# Main.net
KiCad netlist of a schematic drawn in Altium Designer
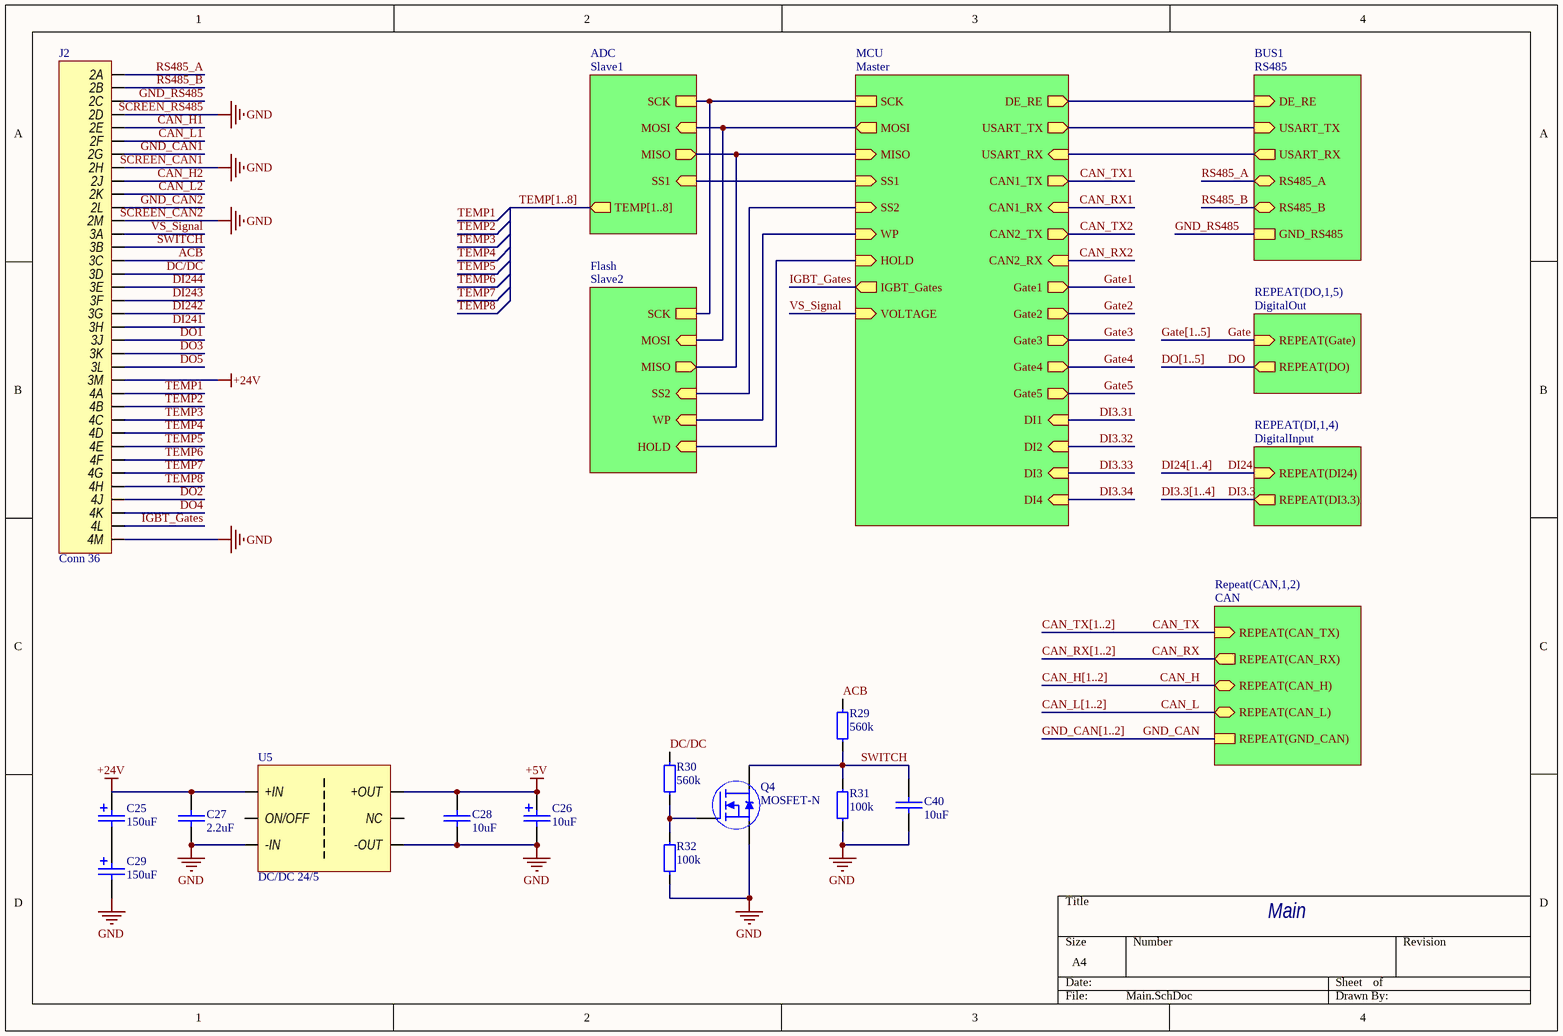
[diagram p0: Main.SchDoc]

(export (version "E")
  (design (tool "Eeschema 10.0.6"))
  (components
    (comp (ref "C25")
      (value "150uF")
      (footprint "TANTAL_D_CASE")
      (description "TECAP, 150uF, 16V, case D, 10%")
      (fields (field (name "PART NUMBER") "293D157X9010D2TE3") (field (name "MANUFACTURER") "Vishay"))
      (libsource (lib "БУНЭ") (part "Cap Tantal 150uF (SMDD)"))
    )
    (comp (ref "C26")
      (value "10uF")
      (footprint "TANTAL_C_CASE")
      (description "TECAP, 10uF, 35V, case C, 10%")
      (fields (field (name "PART NUMBER") "TECAP10/35VC10") (field (name "MANUFACTURER") "China"))
      (libsource (lib "БУНЭ") (part "Cap Tantal 10uF (SMDC)"))
    )
    (comp (ref "C27")
      (value "2.2uF")
      (footprint "0603 Capicator")
      (description "2.2uF X5R 50V 10% 0603")
      (fields
        (field (name "MANUFACTURER") "Murata Manufacturing")
        (field (name "PART NUMBER") "GRM188R61H225KE11D")
      )
      (libsource (lib "БУНЭ") (part "Cap 2.2uF (0603)"))
    )
    (comp (ref "C28")
      (value "10uF")
      (footprint "0603 Capicator")
      (description "10uF X5R 25V 20% 0603")
      (fields
        (field (name "MANUFACTURER") "Murata Manufacturing")
        (field (name "PART NUMBER") "GRM188R61E106M")
      )
      (libsource (lib "БУНЭ") (part "Cap 10uF (0603)"))
    )
    (comp (ref "C29")
      (value "150uF")
      (footprint "TANTAL_D_CASE")
      (description "TECAP, 150uF, 16V, case D, 10%")
      (fields (field (name "PART NUMBER") "293D157X9010D2TE3") (field (name "MANUFACTURER") "Vishay"))
      (libsource (lib "БУНЭ") (part "Cap Tantal 150uF (SMDD)"))
    )
    (comp (ref "C40")
      (value "10uF")
      (footprint "0603 Capicator")
      (description "10uF X5R 25V 20% 0603")
      (fields
        (field (name "MANUFACTURER") "Murata Manufacturing")
        (field (name "PART NUMBER") "GRM188R61E106M")
      )
      (libsource (lib "БУНЭ") (part "Cap 10uF (0603)"))
    )
    (comp (ref "J2")
      (value "Conn 36")
      (footprint "Molex_477320361")
      (description "Molec 36 pin PCB Header 477320361")
      (fields (field (name "MANUFACTURER") "Molex") (field (name "PART NUMBER") "477320361"))
      (libsource (lib "БУНЭ") (part "Conn 36 (Molex)"))
    )
    (comp (ref "Q4")
      (value "MOSFET-N")
      (footprint "SOT-23")
      (description "VDS 30V,  VGS Max ± 20V, RDS 27-40mΩ,")
      (fields
        (field (name "PART NUMBER") "IRLML0030TRPBF")
        (field (name "MANUFACTURER") "Infineon Technologies")
      )
      (libsource (lib "БУНЭ") (part "MOSFET-N [IRLML]"))
    )
    (comp (ref "R29")
      (value "560k")
      (footprint "0603 Resistor")
      (description "0.1W 0603 560k, 1%")
      (fields (field (name "PART NUMBER") "RC0603FR-07560KL") (field (name "MANUFACTURER") "Taiwan"))
      (libsource (lib "БУНЭ") (part "Res 560k (0603)"))
    )
    (comp (ref "R30")
      (value "560k")
      (footprint "0603 Resistor")
      (description "0.1W 0603 560k, 1%")
      (fields (field (name "PART NUMBER") "RC0603FR-07560KL") (field (name "MANUFACTURER") "Taiwan"))
      (libsource (lib "БУНЭ") (part "Res 560k (0603)"))
    )
    (comp (ref "R31")
      (value "100k")
      (footprint "0603 Resistor")
      (description "0.1W 0603 100k, 1%")
      (fields (field (name "PART NUMBER") "RC0603FR-07100KL") (field (name "MANUFACTURER") "Taiwan"))
      (libsource (lib "БУНЭ") (part "Res 100k (0603)"))
    )
    (comp (ref "R32")
      (value "100k")
      (footprint "0603 Resistor")
      (description "0.1W 0603 100k, 1%")
      (fields (field (name "PART NUMBER") "RC0603FR-07100KL") (field (name "MANUFACTURER") "Taiwan"))
      (libsource (lib "БУНЭ") (part "Res 100k (0603)"))
    )
    (comp (ref "U5")
      (value "DC/DC 24/5")
      (footprint "VDRI10(6)")
      (description "DC/DC converter 24/5 10W")
      (fields (field (name "MANUFACTURER") "Voltbricks") (field (name "PART NUMBER") "VDRI10B05"))
      (libsource (lib "БУНЭ") (part "VDRI10B05"))
    )
  )
  (nets
    (net (code "1") (name "+5V") (class "Default")
      (node (ref "C26") (pin "2") (pinfunction "2_2") (pintype "passive"))
      (node (ref "C28") (pin "2") (pinfunction "2_2") (pintype "passive"))
      (node (ref "U5") (pin "9") (pinfunction "+OUT_9") (pintype "passive"))
    )
    (net (code "2") (name "+24V") (class "Default")
      (node (ref "C25") (pin "2") (pinfunction "2_2") (pintype "passive"))
      (node (ref "C27") (pin "2") (pinfunction "2_2") (pintype "passive"))
      (node (ref "J2") (pin "3M") (pinfunction "3M_3M") (pintype "passive"))
      (node (ref "U5") (pin "16") (pinfunction "+IN_16") (pintype "passive"))
    )
    (net (code "3") (name "/ACB") (class "Default")
      (node (ref "J2") (pin "3C") (pinfunction "3C_3C") (pintype "passive"))
      (node (ref "R29") (pin "2") (pinfunction "2_2") (pintype "passive"))
    )
    (net (code "5") (name "/CAN_H1") (class "Default")
      (node (ref "J2") (pin "2E") (pinfunction "2E_2E") (pintype "passive"))
    )
    (net (code "6") (name "/CAN_H2") (class "Default")
      (node (ref "J2") (pin "2J") (pinfunction "2J_2J") (pintype "passive"))
    )
    (net (code "9") (name "/CAN_L1") (class "Default")
      (node (ref "J2") (pin "2F") (pinfunction "2F_2F") (pintype "passive"))
    )
    (net (code "10") (name "/CAN_L2") (class "Default")
      (node (ref "J2") (pin "2K") (pinfunction "2K_2K") (pintype "passive"))
    )
    (net (code "20") (name "/DC{slash}DC") (class "Default")
      (node (ref "J2") (pin "3D") (pinfunction "3D_3D") (pintype "passive"))
      (node (ref "R30") (pin "2") (pinfunction "2_2") (pintype "passive"))
    )
    (net (code "30") (name "/DI241") (class "Default")
      (node (ref "J2") (pin "3H") (pinfunction "3H_3H") (pintype "passive"))
    )
    (net (code "31") (name "/DI242") (class "Default")
      (node (ref "J2") (pin "3G") (pinfunction "3G_3G") (pintype "passive"))
    )
    (net (code "32") (name "/DI243") (class "Default")
      (node (ref "J2") (pin "3F") (pinfunction "3F_3F") (pintype "passive"))
    )
    (net (code "33") (name "/DI244") (class "Default")
      (node (ref "J2") (pin "3E") (pinfunction "3E_3E") (pintype "passive"))
    )
    (net (code "35") (name "/DO1") (class "Default")
      (node (ref "J2") (pin "3J") (pinfunction "3J_3J") (pintype "passive"))
    )
    (net (code "36") (name "/DO2") (class "Default")
      (node (ref "J2") (pin "4J") (pinfunction "4J_4J") (pintype "passive"))
    )
    (net (code "37") (name "/DO3") (class "Default")
      (node (ref "J2") (pin "3K") (pinfunction "3K_3K") (pintype "passive"))
    )
    (net (code "38") (name "/DO4") (class "Default")
      (node (ref "J2") (pin "4K") (pinfunction "4K_4K") (pintype "passive"))
    )
    (net (code "39") (name "/DO5") (class "Default")
      (node (ref "J2") (pin "3L") (pinfunction "3L_3L") (pintype "passive"))
    )
    (net (code "42") (name "/GND_CAN1") (class "Default")
      (node (ref "J2") (pin "2G") (pinfunction "2G_2G") (pintype "passive"))
    )
    (net (code "43") (name "/GND_CAN2") (class "Default")
      (node (ref "J2") (pin "2L") (pinfunction "2L_2L") (pintype "passive"))
    )
    (net (code "45") (name "/GND_RS485") (class "Default")
      (node (ref "J2") (pin "2C") (pinfunction "2C_2C") (pintype "passive"))
    )
    (net (code "54") (name "/IGBT_Gates") (class "Default")
      (node (ref "J2") (pin "4L") (pinfunction "4L_4L") (pintype "passive"))
    )
    (net (code "57") (name "/RS485_A") (class "Default")
      (node (ref "J2") (pin "2A") (pinfunction "2A_2A") (pintype "passive"))
    )
    (net (code "58") (name "/RS485_B") (class "Default")
      (node (ref "J2") (pin "2B") (pinfunction "2B_2B") (pintype "passive"))
    )
    (net (code "62") (name "/SWITCH") (class "Default")
      (node (ref "C40") (pin "2") (pinfunction "2_2") (pintype "passive"))
      (node (ref "J2") (pin "3B") (pinfunction "3B_3B") (pintype "passive"))
      (node (ref "Q4") (pin "3") (pinfunction "Drain_3") (pintype "passive"))
      (node (ref "R29") (pin "1") (pinfunction "1_1") (pintype "passive"))
      (node (ref "R31") (pin "2") (pinfunction "2_2") (pintype "passive"))
    )
    (net (code "63") (name "/TEMP1") (class "Default")
      (node (ref "J2") (pin "4A") (pinfunction "4A_4A") (pintype "passive"))
    )
    (net (code "64") (name "/TEMP2") (class "Default")
      (node (ref "J2") (pin "4B") (pinfunction "4B_4B") (pintype "passive"))
    )
    (net (code "65") (name "/TEMP3") (class "Default")
      (node (ref "J2") (pin "4C") (pinfunction "4C_4C") (pintype "passive"))
    )
    (net (code "66") (name "/TEMP4") (class "Default")
      (node (ref "J2") (pin "4D") (pinfunction "4D_4D") (pintype "passive"))
    )
    (net (code "67") (name "/TEMP5") (class "Default")
      (node (ref "J2") (pin "4E") (pinfunction "4E_4E") (pintype "passive"))
    )
    (net (code "68") (name "/TEMP6") (class "Default")
      (node (ref "J2") (pin "4F") (pinfunction "4F_4F") (pintype "passive"))
    )
    (net (code "69") (name "/TEMP7") (class "Default")
      (node (ref "J2") (pin "4G") (pinfunction "4G_4G") (pintype "passive"))
    )
    (net (code "70") (name "/TEMP8") (class "Default")
      (node (ref "J2") (pin "4H") (pinfunction "4H_4H") (pintype "passive"))
    )
    (net (code "74") (name "/VS_Signal") (class "Default")
      (node (ref "J2") (pin "3A") (pinfunction "3A_3A") (pintype "passive"))
    )
    (net (code "76") (name "GND") (class "Default")
      (node (ref "C26") (pin "1") (pinfunction "1_1") (pintype "passive"))
      (node (ref "C27") (pin "1") (pinfunction "1_1") (pintype "passive"))
      (node (ref "C28") (pin "1") (pinfunction "1_1") (pintype "passive"))
      (node (ref "C29") (pin "1") (pinfunction "1_1") (pintype "passive"))
      (node (ref "C40") (pin "1") (pinfunction "1_1") (pintype "passive"))
      (node (ref "J2") (pin "2D") (pinfunction "2D_2D") (pintype "passive"))
      (node (ref "J2") (pin "2H") (pinfunction "2H_2H") (pintype "passive"))
      (node (ref "J2") (pin "2M") (pinfunction "2M_2M") (pintype "passive"))
      (node (ref "J2") (pin "4M") (pinfunction "4M_4M") (pintype "passive"))
      (node (ref "Q4") (pin "2") (pinfunction "Source_2") (pintype "passive"))
      (node (ref "R31") (pin "1") (pinfunction "1_1") (pintype "passive"))
      (node (ref "R32") (pin "1") (pinfunction "1_1") (pintype "passive"))
      (node (ref "U5") (pin "1") (pinfunction "-IN_1") (pintype "passive"))
      (node (ref "U5") (pin "10") (pinfunction "-OUT_10") (pintype "passive"))
    )
    (net (code "77") (name "Net-(C25-Pad1)") (class "Default")
      (node (ref "C25") (pin "1") (pinfunction "1_1") (pintype "passive"))
      (node (ref "C29") (pin "2") (pinfunction "2_2") (pintype "passive"))
    )
    (net (code "78") (name "Net-(Q4-Gate)") (class "Default")
      (node (ref "Q4") (pin "1") (pinfunction "Gate_1") (pintype "passive"))
      (node (ref "R30") (pin "1") (pinfunction "1_1") (pintype "passive"))
      (node (ref "R32") (pin "2") (pinfunction "2_2") (pintype "passive"))
    )
    (net (code "79") (name "unconnected-(U5-NC-Pad8)") (class "Default")
      (node (ref "U5") (pin "8") (pinfunction "NC_8") (pintype "passive"))
    )
    (net (code "80") (name "unconnected-(U5-ON{slash}OFF-Pad2)") (class "Default")
      (node (ref "U5") (pin "2") (pinfunction "ON/OFF_2") (pintype "passive"))
    )
  )
)
